# CLK_SYNTH.net
KiCad netlist of a schematic drawn in Altium Designer
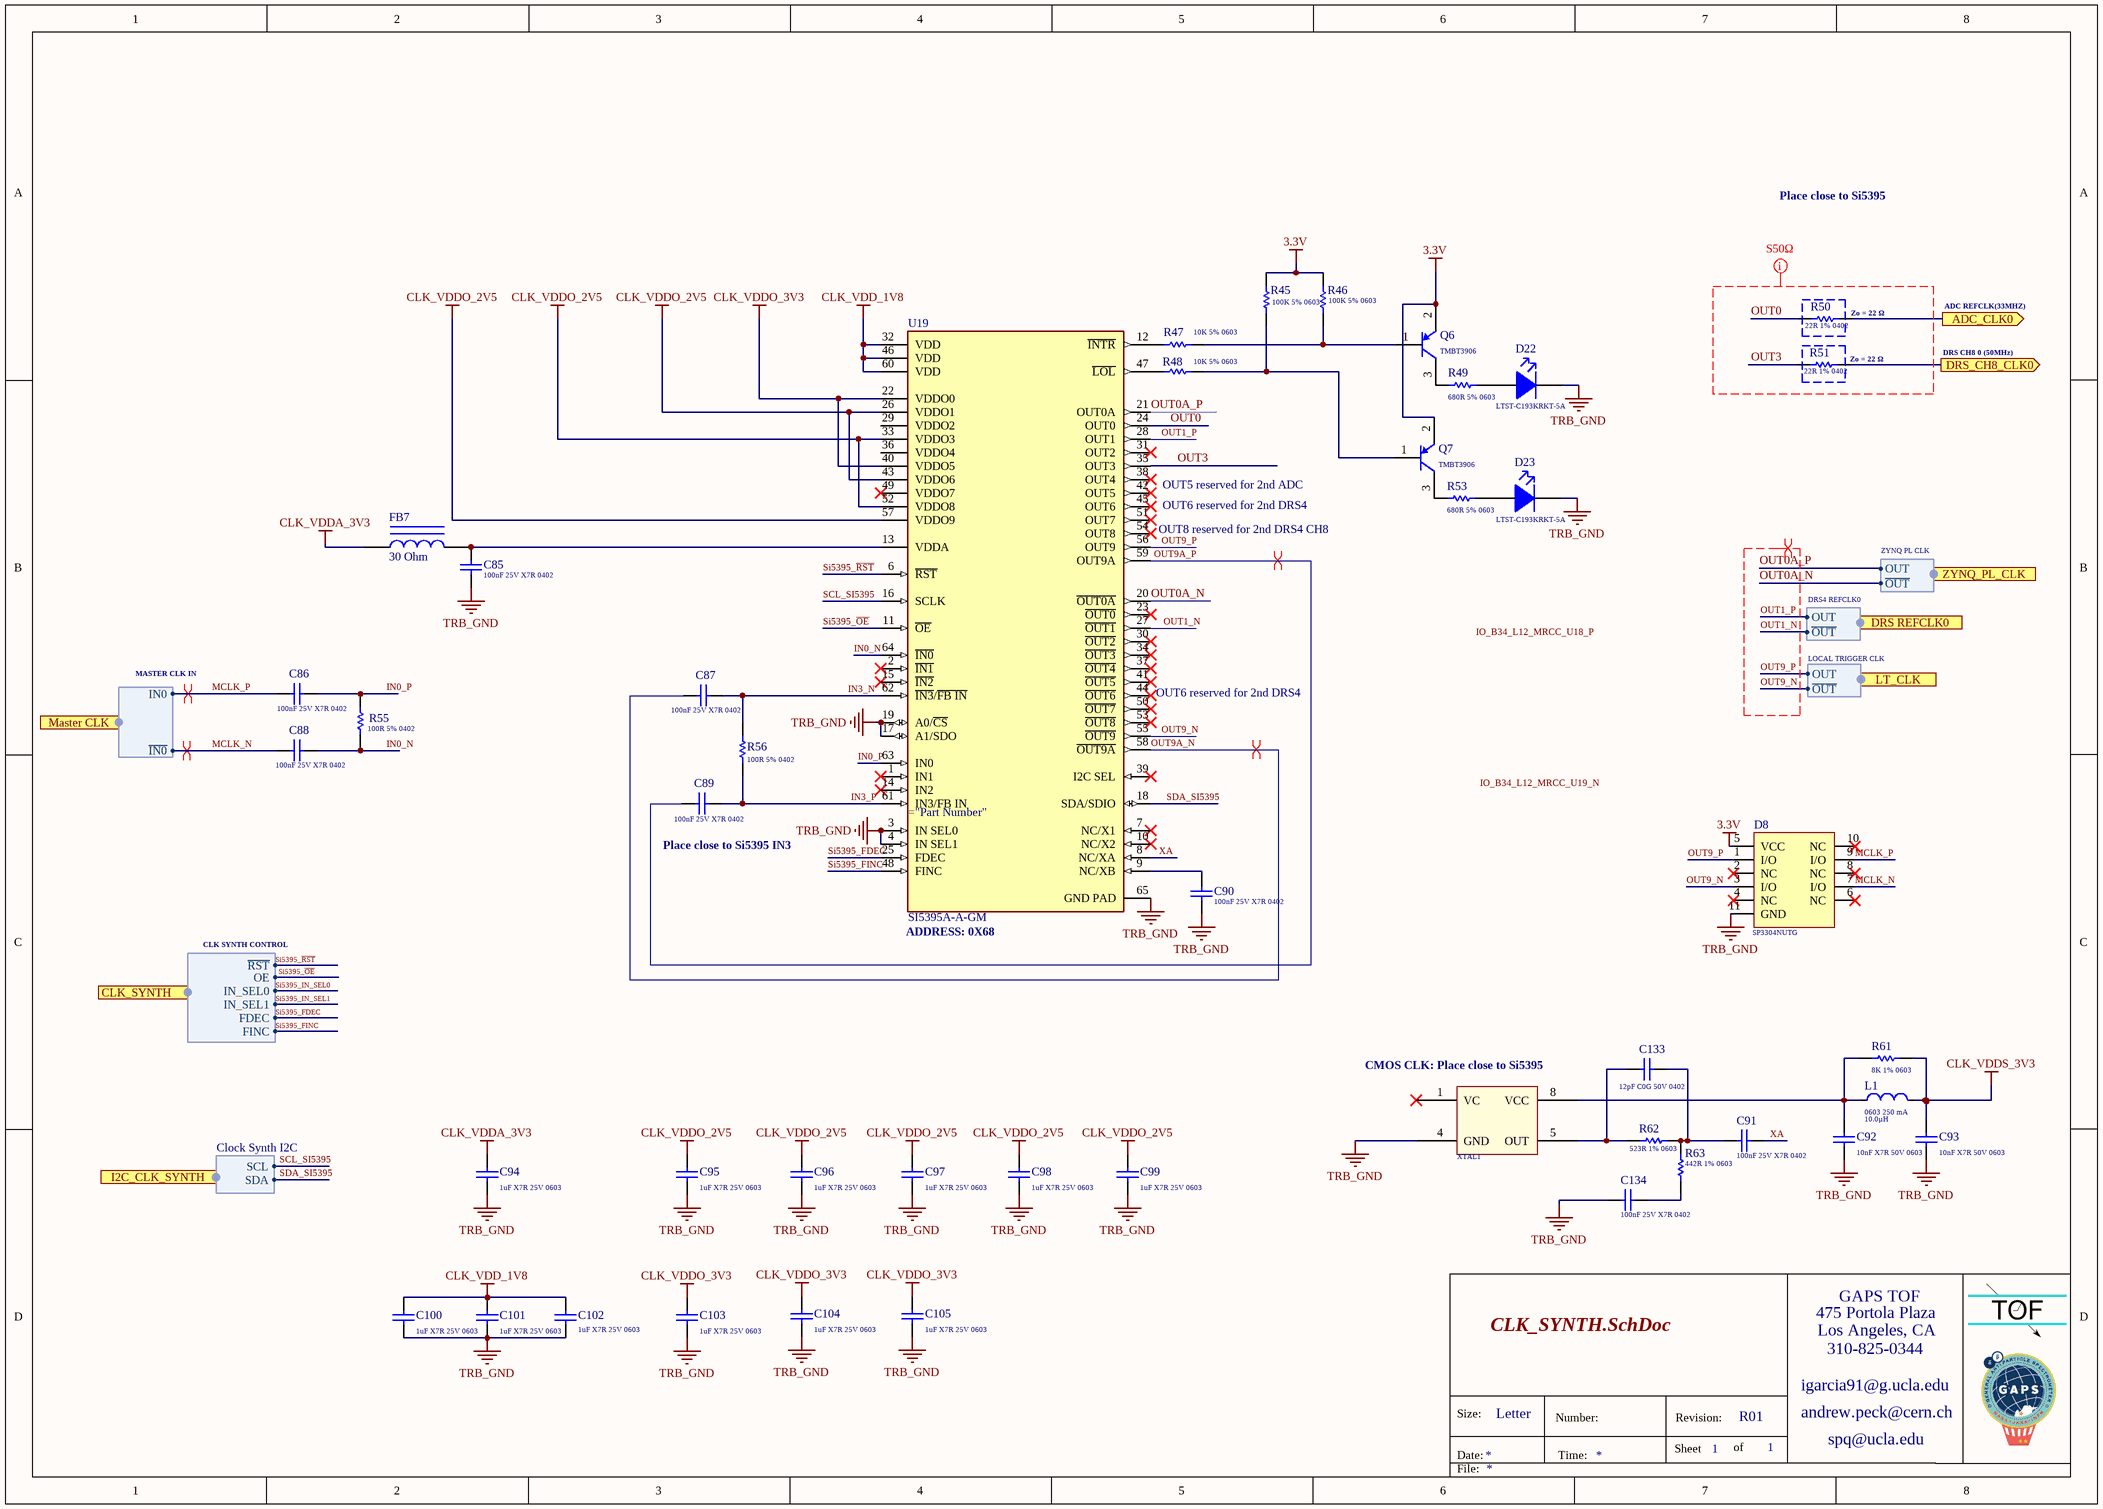
[diagram p0: CLK_SYNTH.SchDoc]

(export (version "E")
  (design (tool "Eeschema 10.0.6"))
  (components
    (comp (ref "C85")
      (value "Cap_Taiyo_Yuden_TMK105B7104KV-FR_100nF")
      (footprint "Cap_Taiyo_Yuden_TMK105B7104KV-FR_100nF")
      (description "CAP CER 100nF 25V X7R 0402")
      (fields (field (name "CAPACITANCE") "100nF 25V X7R 0402"))
      (libsource (lib "Cap_Taiyo_Yuden_TMK105B7104KV-FR_100nF") (part "Cap_Taiyo_Yuden_TMK105B7104KV-FR_100nF"))
    )
    (comp (ref "C86")
      (value "Cap_Taiyo_Yuden_TMK105B7104KV-FR_100nF")
      (footprint "Cap_Taiyo_Yuden_TMK105B7104KV-FR_100nF")
      (description "CAP CER 100nF 25V X7R 0402")
      (fields (field (name "CAPACITANCE") "100nF 25V X7R 0402"))
      (libsource (lib "Cap_Taiyo_Yuden_TMK105B7104KV-FR_100nF") (part "Cap_Taiyo_Yuden_TMK105B7104KV-FR_100nF"))
    )
    (comp (ref "C87")
      (value "Cap_Taiyo_Yuden_TMK105B7104KV-FR_100nF")
      (footprint "Cap_Taiyo_Yuden_TMK105B7104KV-FR_100nF")
      (description "CAP CER 100nF 25V X7R 0402")
      (fields (field (name "CAPACITANCE") "100nF 25V X7R 0402"))
      (libsource (lib "Cap_Taiyo_Yuden_TMK105B7104KV-FR_100nF") (part "Cap_Taiyo_Yuden_TMK105B7104KV-FR_100nF"))
    )
    (comp (ref "C88")
      (value "Cap_Taiyo_Yuden_TMK105B7104KV-FR_100nF")
      (footprint "Cap_Taiyo_Yuden_TMK105B7104KV-FR_100nF")
      (description "CAP CER 100nF 25V X7R 0402")
      (fields (field (name "CAPACITANCE") "100nF 25V X7R 0402"))
      (libsource (lib "Cap_Taiyo_Yuden_TMK105B7104KV-FR_100nF") (part "Cap_Taiyo_Yuden_TMK105B7104KV-FR_100nF"))
    )
    (comp (ref "C89")
      (value "Cap_Taiyo_Yuden_TMK105B7104KV-FR_100nF")
      (footprint "Cap_Taiyo_Yuden_TMK105B7104KV-FR_100nF")
      (description "CAP CER 100nF 25V X7R 0402")
      (fields (field (name "CAPACITANCE") "100nF 25V X7R 0402"))
      (libsource (lib "Cap_Taiyo_Yuden_TMK105B7104KV-FR_100nF") (part "Cap_Taiyo_Yuden_TMK105B7104KV-FR_100nF"))
    )
    (comp (ref "C90")
      (value "Cap_Taiyo_Yuden_TMK105B7104KV-FR_100nF")
      (footprint "Cap_Taiyo_Yuden_TMK105B7104KV-FR_100nF")
      (description "CAP CER 100nF 25V X7R 0402")
      (fields (field (name "CAPACITANCE") "100nF 25V X7R 0402"))
      (libsource (lib "Cap_Taiyo_Yuden_TMK105B7104KV-FR_100nF") (part "Cap_Taiyo_Yuden_TMK105B7104KV-FR_100nF"))
    )
    (comp (ref "C91")
      (value "Cap_Taiyo_Yuden_TMK105B7104KV-FR_100nF")
      (footprint "Cap_Taiyo_Yuden_TMK105B7104KV-FR_100nF")
      (description "CAP CER 100nF 25V X7R 0402")
      (fields (field (name "CAPACITANCE") "100nF 25V X7R 0402"))
      (libsource (lib "Cap_Taiyo_Yuden_TMK105B7104KV-FR_100nF") (part "Cap_Taiyo_Yuden_TMK105B7104KV-FR_100nF"))
    )
    (comp (ref "C92")
      (value "Cap_Kemet_C0603C103J5RACTU_eec")
      (footprint "Kemet_C0603_0")
      (description "CAP CER 10nF 50V X7R 0603")
      (fields
        (field (name "PART NUMBER") "C0603C103J5RACTU")
        (field (name "MANUFACTURER") "Kemet")
        (field (name "CAPACITANCE") "10nF X7R 50V 0603")
      )
      (libsource (lib "Cap_Kemet_C0603C103J5RACTU_10nF") (part "Cap_Kemet_C0603C103J5RACTU_eec"))
    )
    (comp (ref "C93")
      (value "Cap_Kemet_C0603C103J5RACTU_eec")
      (footprint "Kemet_C0603_0")
      (description "CAP CER 10nF 50V X7R 0603")
      (fields
        (field (name "PART NUMBER") "C0603C103J5RACTU")
        (field (name "MANUFACTURER") "Kemet")
        (field (name "CAPACITANCE") "10nF X7R 50V 0603")
      )
      (libsource (lib "Cap_Kemet_C0603C103J5RACTU_10nF") (part "Cap_Kemet_C0603C103J5RACTU_eec"))
    )
    (comp (ref "C94")
      (value "Cap_Murata_GCJ188R71E105KA01J_1uF")
      (footprint "Cap_Murata_GCJ188R71E105KA01J_1uF")
      (description "CAP CER 1uF 25V X7R 0603")
      (fields (field (name "CAPACITANCE") "1uF X7R 25V 0603"))
      (libsource (lib "Cap_Murata_GCJ188R71E105KA01J_1uF") (part "Cap_Murata_GCJ188R71E105KA01J_1uF"))
    )
    (comp (ref "C95")
      (value "Cap_Murata_GCJ188R71E105KA01J_1uF")
      (footprint "Cap_Murata_GCJ188R71E105KA01J_1uF")
      (description "CAP CER 1uF 25V X7R 0603")
      (fields (field (name "CAPACITANCE") "1uF X7R 25V 0603"))
      (libsource (lib "Cap_Murata_GCJ188R71E105KA01J_1uF") (part "Cap_Murata_GCJ188R71E105KA01J_1uF"))
    )
    (comp (ref "C96")
      (value "Cap_Murata_GCJ188R71E105KA01J_1uF")
      (footprint "Cap_Murata_GCJ188R71E105KA01J_1uF")
      (description "CAP CER 1uF 25V X7R 0603")
      (fields (field (name "CAPACITANCE") "1uF X7R 25V 0603"))
      (libsource (lib "Cap_Murata_GCJ188R71E105KA01J_1uF") (part "Cap_Murata_GCJ188R71E105KA01J_1uF"))
    )
    (comp (ref "C97")
      (value "Cap_Murata_GCJ188R71E105KA01J_1uF")
      (footprint "Cap_Murata_GCJ188R71E105KA01J_1uF")
      (description "CAP CER 1uF 25V X7R 0603")
      (fields (field (name "CAPACITANCE") "1uF X7R 25V 0603"))
      (libsource (lib "Cap_Murata_GCJ188R71E105KA01J_1uF") (part "Cap_Murata_GCJ188R71E105KA01J_1uF"))
    )
    (comp (ref "C98")
      (value "Cap_Murata_GCJ188R71E105KA01J_1uF")
      (footprint "Cap_Murata_GCJ188R71E105KA01J_1uF")
      (description "CAP CER 1uF 25V X7R 0603")
      (fields (field (name "CAPACITANCE") "1uF X7R 25V 0603"))
      (libsource (lib "Cap_Murata_GCJ188R71E105KA01J_1uF") (part "Cap_Murata_GCJ188R71E105KA01J_1uF"))
    )
    (comp (ref "C99")
      (value "Cap_Murata_GCJ188R71E105KA01J_1uF")
      (footprint "Cap_Murata_GCJ188R71E105KA01J_1uF")
      (description "CAP CER 1uF 25V X7R 0603")
      (fields (field (name "CAPACITANCE") "1uF X7R 25V 0603"))
      (libsource (lib "Cap_Murata_GCJ188R71E105KA01J_1uF") (part "Cap_Murata_GCJ188R71E105KA01J_1uF"))
    )
    (comp (ref "C100")
      (value "Cap_Murata_GCJ188R71E105KA01J_1uF")
      (footprint "Cap_Murata_GCJ188R71E105KA01J_1uF")
      (description "CAP CER 1uF 25V X7R 0603")
      (fields (field (name "CAPACITANCE") "1uF X7R 25V 0603"))
      (libsource (lib "Cap_Murata_GCJ188R71E105KA01J_1uF") (part "Cap_Murata_GCJ188R71E105KA01J_1uF"))
    )
    (comp (ref "C101")
      (value "Cap_Murata_GCJ188R71E105KA01J_1uF")
      (footprint "Cap_Murata_GCJ188R71E105KA01J_1uF")
      (description "CAP CER 1uF 25V X7R 0603")
      (fields (field (name "CAPACITANCE") "1uF X7R 25V 0603"))
      (libsource (lib "Cap_Murata_GCJ188R71E105KA01J_1uF") (part "Cap_Murata_GCJ188R71E105KA01J_1uF"))
    )
    (comp (ref "C102")
      (value "Cap_Murata_GCJ188R71E105KA01J_1uF")
      (footprint "Cap_Murata_GCJ188R71E105KA01J_1uF")
      (description "CAP CER 1uF 25V X7R 0603")
      (fields (field (name "CAPACITANCE") "1uF X7R 25V 0603"))
      (libsource (lib "Cap_Murata_GCJ188R71E105KA01J_1uF") (part "Cap_Murata_GCJ188R71E105KA01J_1uF"))
    )
    (comp (ref "C103")
      (value "Cap_Murata_GCJ188R71E105KA01J_1uF")
      (footprint "Cap_Murata_GCJ188R71E105KA01J_1uF")
      (description "CAP CER 1uF 25V X7R 0603")
      (fields (field (name "CAPACITANCE") "1uF X7R 25V 0603"))
      (libsource (lib "Cap_Murata_GCJ188R71E105KA01J_1uF") (part "Cap_Murata_GCJ188R71E105KA01J_1uF"))
    )
    (comp (ref "C104")
      (value "Cap_Murata_GCJ188R71E105KA01J_1uF")
      (footprint "Cap_Murata_GCJ188R71E105KA01J_1uF")
      (description "CAP CER 1uF 25V X7R 0603")
      (fields (field (name "CAPACITANCE") "1uF X7R 25V 0603"))
      (libsource (lib "Cap_Murata_GCJ188R71E105KA01J_1uF") (part "Cap_Murata_GCJ188R71E105KA01J_1uF"))
    )
    (comp (ref "C105")
      (value "Cap_Murata_GCJ188R71E105KA01J_1uF")
      (footprint "Cap_Murata_GCJ188R71E105KA01J_1uF")
      (description "CAP CER 1uF 25V X7R 0603")
      (fields (field (name "CAPACITANCE") "1uF X7R 25V 0603"))
      (libsource (lib "Cap_Murata_GCJ188R71E105KA01J_1uF") (part "Cap_Murata_GCJ188R71E105KA01J_1uF"))
    )
    (comp (ref "C133")
      (value "Cap_Murata_GCQ1555C1H120FB01D_12pF")
      (footprint "Cap_Murata_GCQ1555C1H120FB01D_12pF")
      (description "Multilayer Ceramic Capacitors MLCC - SMD/SMT 0402 50VDC 12pF 1% AEC-Q200")
      (fields (field (name "CAPACITANCE") "12pF C0G 50V 0402"))
      (libsource (lib "Cap_Murata_GCQ1555C1H120FB01D_12pF") (part "Cap_Murata_GCQ1555C1H120FB01D_12pF"))
    )
    (comp (ref "C134")
      (value "Cap_Taiyo_Yuden_TMK105B7104KV-FR_100nF")
      (footprint "Cap_Taiyo_Yuden_TMK105B7104KV-FR_100nF")
      (description "CAP CER 100nF 25V X7R 0402")
      (fields (field (name "CAPACITANCE") "100nF 25V X7R 0402"))
      (libsource (lib "Cap_Taiyo_Yuden_TMK105B7104KV-FR_100nF") (part "Cap_Taiyo_Yuden_TMK105B7104KV-FR_100nF"))
    )
    (comp (ref "D8")
      (value "ESD_LittleFuse_SP3304NUTG_3V3")
      (footprint "ESD_LittleFuse_SP3304NUTG_3V3")
      (description "ESD Suppressors / TVS Diodes 4CH 20A 3.3V 3.5pF Lightning Protection")
      (fields (field (name "SERIES") "SP3304NUTG"))
      (libsource (lib "ESD_LittleFuse_SP3304NUTG _3V3") (part "ESD_LittleFuse_SP3304NUTG_3V3"))
    )
    (comp (ref "D22")
      (value "LTST-C193KRKT-5A")
      (footprint "Led_Lite-On_LTST-C193KGKT-5A_Red")
      (description "Standard LEDs - SMD Red 470nm 28mcd 20mA")
      (fields (field (name "SERIES") "LTST-C193KRKT-5A"))
      (libsource (lib "Led_Lite-On_LTST-C193KGKT-5A_Red") (part "Led_Lite-On_LTST-C193KGKT-5A_Red"))
    )
    (comp (ref "D23")
      (value "LTST-C193KRKT-5A")
      (footprint "Led_Lite-On_LTST-C193KGKT-5A_Red")
      (description "Standard LEDs - SMD Red 470nm 28mcd 20mA")
      (fields (field (name "SERIES") "LTST-C193KRKT-5A"))
      (libsource (lib "Led_Lite-On_LTST-C193KGKT-5A_Red") (part "Led_Lite-On_LTST-C193KGKT-5A_Red"))
    )
    (comp (ref "FB7")
      (value "30 Ohm")
      (footprint "Feb_MURATA_BLM15AX300SZ1D_30")
      (description "Feb SMD 30 OHM 25% 3/4W 0402")
      (libsource (lib "Feb_MURATA_BLM15AX300SZ1D_30") (part "Feb_MURATA_BLM15AX300SZ1D_30"))
    )
    (comp (ref "L1")
      (value "0603 250 mA")
      (footprint "TDK_MLZ1608M100WT_0")
      (description "IND 10µH Shielded Multilayer Inductor 250mA 1.365 Ohm Max 0603 (1608 Metric)")
      (fields
        (field (name "PART NUMBER") "MLZ1608M100WT")
        (field (name "MANUFACTURER") "TDK")
        (field (name "INDUCTANCE") "10.0µH")
      )
      (libsource (lib "Ind_TDK_MLZ1608M100WT_10uH") (part "Ind_TDK_MLZ1608M100WT_eec"))
    )
    (comp (ref "Q6")
      (value "BJT_PNP_Toshiba_TMBT3906")
      (footprint "BJT_PNP_Toshiba_TMBT3906")
      (description "Bipolar Transistors - BJT Transistor for Low Freq. Amplification")
      (fields (field (name "SERIES") "TMBT3906"))
      (libsource (lib "BJT_PNP_Toshiba_TMBT3906") (part "BJT_PNP_Toshiba_TMBT3906"))
    )
    (comp (ref "Q7")
      (value "BJT_PNP_Toshiba_TMBT3906")
      (footprint "BJT_PNP_Toshiba_TMBT3906")
      (description "Bipolar Transistors - BJT Transistor for Low Freq. Amplification")
      (fields (field (name "SERIES") "TMBT3906"))
      (libsource (lib "BJT_PNP_Toshiba_TMBT3906") (part "BJT_PNP_Toshiba_TMBT3906"))
    )
    (comp (ref "R45")
      (value "100K 5% 0603")
      (footprint "RESC0603(1608)_N")
      (description "100K 0.1W 5% 0603 (1608 Metric)  SMD")
      (fields (field (name "TOLERANCE") "5 %") (field (name "POWER") "0.1 W"))
      (libsource (lib "Altium Content Vault") (part "RES"))
    )
    (comp (ref "R46")
      (value "100K 5% 0603")
      (footprint "RESC0603(1608)_N")
      (description "100K 0.1W 5% 0603 (1608 Metric)  SMD")
      (fields (field (name "TOLERANCE") "5 %") (field (name "POWER") "0.1 W"))
      (libsource (lib "Altium Content Vault") (part "RES"))
    )
    (comp (ref "R47")
      (value "10K 5% 0603")
      (footprint "RESC0603(1608)_L")
      (description "10K 0.1W 5% 0603 (1608 Metric)  SMD")
      (fields (field (name "TOLERANCE") "5 %") (field (name "POWER") "0.1 W"))
      (libsource (lib "Altium Content Vault") (part "RES"))
    )
    (comp (ref "R48")
      (value "10K 5% 0603")
      (footprint "RESC0603(1608)_L")
      (description "10K 0.1W 5% 0603 (1608 Metric)  SMD")
      (fields (field (name "TOLERANCE") "5 %") (field (name "POWER") "0.1 W"))
      (libsource (lib "Altium Content Vault") (part "RES"))
    )
    (comp (ref "R49")
      (value "680R 5% 0603")
      (footprint "RESC0603(1608)_L")
      (description "680R 0.1W 5% 0603 (1608 Metric)  SMD")
      (fields (field (name "TOLERANCE") "5 %") (field (name "POWER") "0.1 W"))
      (libsource (lib "Altium Content Vault") (part "RES"))
    )
    (comp (ref "R50")
      (value "22R 1% 0402")
      (footprint "RESC0402(1005)_L")
      (description "22R 0.063W 1% 0402 (1005 Metric)  SMD")
      (fields (field (name "TOLERANCE") "1 %") (field (name "POWER") "0.063 W"))
      (libsource (lib "Altium Content Vault") (part "RES"))
    )
    (comp (ref "R51")
      (value "22R 1% 0402")
      (footprint "RESC0402(1005)_L")
      (description "22R 0.063W 1% 0402 (1005 Metric)  SMD")
      (fields (field (name "TOLERANCE") "1 %") (field (name "POWER") "0.063 W"))
      (libsource (lib "Altium Content Vault") (part "RES"))
    )
    (comp (ref "R53")
      (value "680R 5% 0603")
      (footprint "RESC0603(1608)_L")
      (description "680R 0.1W 5% 0603 (1608 Metric)  SMD")
      (fields (field (name "TOLERANCE") "5 %") (field (name "POWER") "0.1 W"))
      (libsource (lib "Altium Content Vault") (part "RES"))
    )
    (comp (ref "R55")
      (value "100R 5% 0402")
      (footprint "RESC0402(1005)_L")
      (description "100R 0.063W 5% 0402 (1005 Metric)  SMD")
      (fields (field (name "TOLERANCE") "5 %") (field (name "POWER") "0.063 W"))
      (libsource (lib "Altium Content Vault") (part "RES"))
    )
    (comp (ref "R56")
      (value "100R 5% 0402")
      (footprint "RESC0402(1005)_L")
      (description "100R 0.063W 5% 0402 (1005 Metric)  SMD")
      (fields (field (name "TOLERANCE") "5 %") (field (name "POWER") "0.063 W"))
      (libsource (lib "Altium Content Vault") (part "RES"))
    )
    (comp (ref "R61")
      (value "8K 1% 0603")
      (footprint "Res_Yageo_RT0603BRE078KL_8K")
      (description "8K 0.1W 1% 0603 (1608 Metric)  SMD")
      (libsource (lib "Res_Yageo_RT0603BRE078KL_8K") (part "Res_Yageo_RT0603BRE078KL_8K"))
    )
    (comp (ref "R62")
      (value "Res_Vishay_CRCW0603523RFKEA_523Ohm")
      (footprint "Res_Vishay_CRCW0603523RFKEA_523Ohm")
      (description "RES SMD 523 OHM 1% 1/10W 0603")
      (fields (field (name "RESISTANCE") "523R 1% 0603"))
      (libsource (lib "Res_Vishay_CRCW0603523RFKEA_523Ohm") (part "Res_Vishay_CRCW0603523RFKEA_523Ohm"))
    )
    (comp (ref "R63")
      (value "Res_Bourns_CR0603-FX-4420ELF_442Ohm")
      (footprint "Res_Bourns_CR0603-FX-4420ELF_442Ohm")
      (description "RES SMD 442 OHM 1% 1/10W 0603")
      (fields (field (name "RESISTANCE") "442R 1% 0603"))
      (libsource (lib "Res_Bourns_CR0603-FX-4420ELF_442Ohm") (part "Res_Bourns_CR0603-FX-4420ELF_442Ohm"))
    )
    (comp (ref "U19")
      (value "IC_Silicon_Laboratories_ SI5395A-A-GM_CLK")
      (footprint "Si5395")
      (fields (field (name "SERIES") "SI5395A-A-GM"))
      (libsource (lib "SI5395A-A-GM") (part "IC_Silicon_Laboratories_ SI5395A-A-GM_CLK"))
    )
    (comp (ref "XTAL1")
      (value "TCXO_Murata_XTCLH50M000CHJA3P0_50MHz")
      (footprint "TCXO_Murata_XTCLH50M000CHJA3P0_50MHz")
      (description "TCXO Oscillators 50MHz 5x3.2x1.5mm 0.2ppm max Crystal")
      (libsource (lib "TCXO_Murata_XTCLH50M000CHJA3P0_50MHz") (part "TCXO_Murata_XTCLH50M000CHJA3P0_50MHz"))
    )
  )
  (nets
    (net (code "15") (name "/ADC_CLK0") (class "Default")
      (node (ref "R50") (pin "1") (pinfunction "1_1") (pintype "passive"))
    )
    (net (code "16") (name "/DRS_CH8_CLK0") (class "Default")
      (node (ref "R51") (pin "1") (pinfunction "1_1") (pintype "passive"))
    )
    (net (code "17") (name "/IN0_N") (class "Default")
      (node (ref "C88") (pin "2") (pinfunction "2_2") (pintype "passive"))
      (node (ref "R55") (pin "1") (pinfunction "1_1") (pintype "passive"))
      (node (ref "U19") (pin "64") (pinfunction "~{IN0}_64") (pintype "input"))
    )
    (net (code "18") (name "/IN0_P") (class "Default")
      (node (ref "C86") (pin "2") (pinfunction "2_2") (pintype "passive"))
      (node (ref "R55") (pin "2") (pinfunction "2_2") (pintype "passive"))
      (node (ref "U19") (pin "63") (pinfunction "IN0_63") (pintype "input"))
    )
    (net (code "19") (name "/IN3_N") (class "Default")
      (node (ref "C87") (pin "2") (pinfunction "2_2") (pintype "passive"))
      (node (ref "R56") (pin "2") (pinfunction "2_2") (pintype "passive"))
      (node (ref "U19") (pin "62") (pinfunction "~{IN3}/~{FB_IN}_62") (pintype "input"))
    )
    (net (code "20") (name "/IN3_P") (class "Default")
      (node (ref "C89") (pin "2") (pinfunction "2_2") (pintype "passive"))
      (node (ref "R56") (pin "1") (pinfunction "1_1") (pintype "passive"))
      (node (ref "U19") (pin "61") (pinfunction "IN3/FB_IN_61") (pintype "input"))
    )
    (net (code "23") (name "/MCLK_N") (class "Default")
      (node (ref "C88") (pin "1") (pinfunction "1_1") (pintype "passive"))
      (node (ref "D8") (pin "7") (pinfunction "I/O_7") (pintype "passive"))
    )
    (net (code "24") (name "/MCLK_P") (class "Default")
      (node (ref "C86") (pin "1") (pinfunction "1_1") (pintype "passive"))
      (node (ref "D8") (pin "9") (pinfunction "I/O_9") (pintype "passive"))
    )
    (net (code "25") (name "/OUT0") (class "Default")
      (node (ref "R50") (pin "2") (pinfunction "2_2") (pintype "passive"))
      (node (ref "U19") (pin "24") (pinfunction "OUT0_24") (pintype "output"))
    )
    (net (code "26") (name "/OUT0A_N") (class "Default")
      (node (ref "U19") (pin "20") (pinfunction "~{OUT0A}_20") (pintype "output"))
    )
    (net (code "27") (name "/OUT0A_P") (class "Default")
      (node (ref "U19") (pin "21") (pinfunction "OUT0A_21") (pintype "output"))
    )
    (net (code "28") (name "/OUT1_N") (class "Default")
      (node (ref "U19") (pin "27") (pinfunction "~{OUT1}_27") (pintype "output"))
    )
    (net (code "29") (name "/OUT1_P") (class "Default")
      (node (ref "U19") (pin "28") (pinfunction "OUT1_28") (pintype "output"))
    )
    (net (code "30") (name "/OUT3") (class "Default")
      (node (ref "R51") (pin "2") (pinfunction "2_2") (pintype "passive"))
      (node (ref "U19") (pin "35") (pinfunction "OUT3_35") (pintype "output"))
    )
    (net (code "31") (name "/OUT9A_N") (class "Default")
      (node (ref "C87") (pin "1") (pinfunction "1_1") (pintype "passive"))
      (node (ref "U19") (pin "58") (pinfunction "~{OUT9A}_58") (pintype "output"))
    )
    (net (code "32") (name "/OUT9A_P") (class "Default")
      (node (ref "C89") (pin "1") (pinfunction "1_1") (pintype "passive"))
      (node (ref "U19") (pin "59") (pinfunction "OUT9A_59") (pintype "output"))
    )
    (net (code "33") (name "/OUT9_N") (class "Default")
      (node (ref "D8") (pin "3") (pinfunction "I/O_3") (pintype "passive"))
      (node (ref "U19") (pin "55") (pinfunction "~{OUT9}_55") (pintype "output"))
    )
    (net (code "34") (name "/OUT9_P") (class "Default")
      (node (ref "D8") (pin "1") (pinfunction "I/O_1") (pintype "passive"))
      (node (ref "U19") (pin "56") (pinfunction "OUT9_56") (pintype "output"))
    )
    (net (code "35") (name "/SCL_SI5395") (class "Default")
      (node (ref "U19") (pin "16") (pinfunction "SCLK_16") (pintype "input"))
    )
    (net (code "36") (name "/SDA_SI5395") (class "Default")
      (node (ref "U19") (pin "18") (pinfunction "SDA/SDIO_18") (pintype "bidirectional"))
    )
    (net (code "37") (name "/Si5395_FDEC") (class "Default")
      (node (ref "U19") (pin "25") (pinfunction "FDEC_25") (pintype "input"))
    )
    (net (code "38") (name "/Si5395_FINC") (class "Default")
      (node (ref "U19") (pin "48") (pinfunction "FINC_48") (pintype "input"))
    )
    (net (code "41") (name "/Si5395_~{OE}") (class "Default")
      (node (ref "U19") (pin "11") (pinfunction "~{OE}_11") (pintype "input"))
    )
    (net (code "42") (name "/Si5395_~{RST}") (class "Default")
      (node (ref "U19") (pin "6") (pinfunction "~{RST}_6") (pintype "input"))
    )
    (net (code "43") (name "/XA") (class "Default")
      (node (ref "C91") (pin "2") (pinfunction "2_2") (pintype "passive"))
      (node (ref "U19") (pin "8") (pinfunction "NC/XA_8") (pintype "input"))
    )
    (net (code "50") (name "3.3V") (class "Default")
      (node (ref "D8") (pin "5") (pinfunction "VCC_5") (pintype "passive"))
      (node (ref "Q6") (pin "2") (pinfunction "E_2") (pintype "passive"))
      (node (ref "Q7") (pin "2") (pinfunction "E_2") (pintype "passive"))
      (node (ref "R45") (pin "2") (pinfunction "2_2") (pintype "passive"))
      (node (ref "R46") (pin "2") (pinfunction "2_2") (pintype "passive"))
    )
    (net (code "51") (name "CLK_VDDA_3V3") (class "Default")
      (node (ref "C94") (pin "2") (pinfunction "2_2") (pintype "passive"))
      (node (ref "FB7") (pin "1") (pinfunction "1_1") (pintype "passive"))
    )
    (net (code "52") (name "CLK_VDDO_2V5") (class "Default")
      (node (ref "C95") (pin "2") (pinfunction "2_2") (pintype "passive"))
      (node (ref "C96") (pin "2") (pinfunction "2_2") (pintype "passive"))
      (node (ref "C97") (pin "2") (pinfunction "2_2") (pintype "passive"))
      (node (ref "C98") (pin "2") (pinfunction "2_2") (pintype "passive"))
      (node (ref "C99") (pin "2") (pinfunction "2_2") (pintype "passive"))
      (node (ref "U19") (pin "26") (pinfunction "VDDO1_26") (pintype "power_in"))
      (node (ref "U19") (pin "33") (pinfunction "VDDO3_33") (pintype "power_in"))
      (node (ref "U19") (pin "43") (pinfunction "VDDO6_43") (pintype "power_in"))
      (node (ref "U19") (pin "52") (pinfunction "VDDO8_52") (pintype "power_in"))
      (node (ref "U19") (pin "57") (pinfunction "VDDO9_57") (pintype "power_in"))
    )
    (net (code "53") (name "CLK_VDDO_3V3") (class "Default")
      (node (ref "C103") (pin "2") (pinfunction "2_2") (pintype "passive"))
      (node (ref "C104") (pin "2") (pinfunction "2_2") (pintype "passive"))
      (node (ref "C105") (pin "2") (pinfunction "2_2") (pintype "passive"))
      (node (ref "U19") (pin "22") (pinfunction "VDDO0_22") (pintype "power_in"))
      (node (ref "U19") (pin "40") (pinfunction "VDDO5_40") (pintype "power_in"))
    )
    (net (code "54") (name "CLK_VDDS_3V3") (class "Default")
      (node (ref "C93") (pin "1") (pinfunction "1_1") (pintype "passive"))
      (node (ref "L1") (pin "2") (pinfunction "2_2") (pintype "passive"))
      (node (ref "R61") (pin "2") (pinfunction "2_2") (pintype "passive"))
    )
    (net (code "55") (name "CLK_VDD_1V8") (class "Default")
      (node (ref "C100") (pin "2") (pinfunction "2_2") (pintype "passive"))
      (node (ref "C101") (pin "2") (pinfunction "2_2") (pintype "passive"))
      (node (ref "C102") (pin "2") (pinfunction "2_2") (pintype "passive"))
      (node (ref "U19") (pin "32") (pinfunction "VDD_32") (pintype "power_in"))
      (node (ref "U19") (pin "46") (pinfunction "VDD_46") (pintype "power_in"))
      (node (ref "U19") (pin "60") (pinfunction "VDD_60") (pintype "power_in"))
    )
    (net (code "56") (name "Net-(C133-Pad1)") (class "Default")
      (node (ref "C133") (pin "1") (pinfunction "1_1") (pintype "passive"))
      (node (ref "C91") (pin "1") (pinfunction "1_1") (pintype "passive"))
      (node (ref "R62") (pin "2") (pinfunction "2_2") (pintype "passive"))
      (node (ref "R63") (pin "2") (pinfunction "2_2") (pintype "passive"))
    )
    (net (code "57") (name "Net-(C134-Pad2)") (class "Default")
      (node (ref "C134") (pin "2") (pinfunction "2_2") (pintype "passive"))
      (node (ref "R63") (pin "1") (pinfunction "1_1") (pintype "passive"))
    )
    (net (code "58") (name "Net-(D22-A)") (class "Default")
      (node (ref "D22") (pin "2") (pinfunction "A_2") (pintype "passive"))
      (node (ref "R49") (pin "2") (pinfunction "2_2") (pintype "passive"))
    )
    (net (code "59") (name "Net-(D23-A)") (class "Default")
      (node (ref "D23") (pin "2") (pinfunction "A_2") (pintype "passive"))
      (node (ref "R53") (pin "2") (pinfunction "2_2") (pintype "passive"))
    )
    (net (code "60") (name "Net-(Q6-B)") (class "Default")
      (node (ref "Q6") (pin "1") (pinfunction "B_1") (pintype "passive"))
      (node (ref "R46") (pin "1") (pinfunction "1_1") (pintype "passive"))
      (node (ref "R47") (pin "1") (pinfunction "1_1") (pintype "passive"))
    )
    (net (code "61") (name "Net-(Q6-C)") (class "Default")
      (node (ref "Q6") (pin "3") (pinfunction "C_3") (pintype "passive"))
      (node (ref "R49") (pin "1") (pinfunction "1_1") (pintype "passive"))
    )
    (net (code "62") (name "Net-(Q7-B)") (class "Default")
      (node (ref "Q7") (pin "1") (pinfunction "B_1") (pintype "passive"))
      (node (ref "R45") (pin "1") (pinfunction "1_1") (pintype "passive"))
      (node (ref "R48") (pin "1") (pinfunction "1_1") (pintype "passive"))
    )
    (net (code "63") (name "Net-(Q7-C)") (class "Default")
      (node (ref "Q7") (pin "3") (pinfunction "C_3") (pintype "passive"))
      (node (ref "R53") (pin "1") (pinfunction "1_1") (pintype "passive"))
    )
    (net (code "64") (name "Net-(U19-NC{slash}XB)") (class "Default")
      (node (ref "C90") (pin "2") (pinfunction "2_2") (pintype "passive"))
      (node (ref "U19") (pin "9") (pinfunction "NC/XB_9") (pintype "input"))
    )
    (net (code "65") (name "Net-(U19-VDDA)") (class "Default")
      (node (ref "C85") (pin "2") (pinfunction "2_2") (pintype "passive"))
      (node (ref "FB7") (pin "2") (pinfunction "2_2") (pintype "passive"))
      (node (ref "U19") (pin "13") (pinfunction "VDDA_13") (pintype "power_in"))
    )
    (net (code "66") (name "Net-(U19-~{INTR})") (class "Default")
      (node (ref "R47") (pin "2") (pinfunction "2_2") (pintype "passive"))
      (node (ref "U19") (pin "12") (pinfunction "~{INTR}_12") (pintype "output"))
    )
    (net (code "67") (name "Net-(U19-~{LOL})") (class "Default")
      (node (ref "R48") (pin "2") (pinfunction "2_2") (pintype "passive"))
      (node (ref "U19") (pin "47") (pinfunction "~{LOL}_47") (pintype "output"))
    )
    (net (code "68") (name "Net-(XTAL1-OUT)") (class "Default")
      (node (ref "C133") (pin "2") (pinfunction "2_2") (pintype "passive"))
      (node (ref "R62") (pin "1") (pinfunction "1_1") (pintype "passive"))
      (node (ref "XTAL1") (pin "5") (pinfunction "OUT_5") (pintype "passive"))
    )
    (net (code "69") (name "Net-(XTAL1-VCC)") (class "Default")
      (node (ref "C92") (pin "1") (pinfunction "1_1") (pintype "passive"))
      (node (ref "L1") (pin "1") (pinfunction "1_1") (pintype "passive"))
      (node (ref "R61") (pin "1") (pinfunction "1_1") (pintype "passive"))
      (node (ref "XTAL1") (pin "8") (pinfunction "VCC_8") (pintype "passive"))
    )
    (net (code "70") (name "TRB_GND") (class "Default")
      (node (ref "C100") (pin "1") (pinfunction "1_1") (pintype "passive"))
      (node (ref "C101") (pin "1") (pinfunction "1_1") (pintype "passive"))
      (node (ref "C102") (pin "1") (pinfunction "1_1") (pintype "passive"))
      (node (ref "C103") (pin "1") (pinfunction "1_1") (pintype "passive"))
      (node (ref "C104") (pin "1") (pinfunction "1_1") (pintype "passive"))
      (node (ref "C105") (pin "1") (pinfunction "1_1") (pintype "passive"))
      (node (ref "C134") (pin "1") (pinfunction "1_1") (pintype "passive"))
      (node (ref "C85") (pin "1") (pinfunction "1_1") (pintype "passive"))
      (node (ref "C90") (pin "1") (pinfunction "1_1") (pintype "passive"))
      (node (ref "C92") (pin "2") (pinfunction "2_2") (pintype "passive"))
      (node (ref "C93") (pin "2") (pinfunction "2_2") (pintype "passive"))
      (node (ref "C94") (pin "1") (pinfunction "1_1") (pintype "passive"))
      (node (ref "C95") (pin "1") (pinfunction "1_1") (pintype "passive"))
      (node (ref "C96") (pin "1") (pinfunction "1_1") (pintype "passive"))
      (node (ref "C97") (pin "1") (pinfunction "1_1") (pintype "passive"))
      (node (ref "C98") (pin "1") (pinfunction "1_1") (pintype "passive"))
      (node (ref "C99") (pin "1") (pinfunction "1_1") (pintype "passive"))
      (node (ref "D22") (pin "1") (pinfunction "K_1") (pintype "passive"))
      (node (ref "D23") (pin "1") (pinfunction "K_1") (pintype "passive"))
      (node (ref "D8") (pin "11") (pinfunction "GND_11") (pintype "passive"))
      (node (ref "U19") (pin "17") (pinfunction "A1/SDO_17") (pintype "bidirectional"))
      (node (ref "U19") (pin "19") (pinfunction "A0/~{CS}_19") (pintype "bidirectional"))
      (node (ref "U19") (pin "3") (pinfunction "IN_SEL0_3") (pintype "input"))
      (node (ref "U19") (pin "4") (pinfunction "IN_SEL1_4") (pintype "input"))
      (node (ref "U19") (pin "65") (pinfunction "GND_PAD_65") (pintype "power_in"))
      (node (ref "XTAL1") (pin "4") (pinfunction "GND_4") (pintype "passive"))
    )
    (net (code "71") (name "unconnected-(D8-NC-Pad2)") (class "Default")
      (node (ref "D8") (pin "2") (pinfunction "NC_2") (pintype "passive+no_connect"))
    )
    (net (code "72") (name "unconnected-(D8-NC-Pad4)") (class "Default")
      (node (ref "D8") (pin "4") (pinfunction "NC_4") (pintype "passive+no_connect"))
    )
    (net (code "73") (name "unconnected-(D8-NC-Pad6)") (class "Default")
      (node (ref "D8") (pin "6") (pinfunction "NC_6") (pintype "passive+no_connect"))
    )
    (net (code "74") (name "unconnected-(D8-NC-Pad8)") (class "Default")
      (node (ref "D8") (pin "8") (pinfunction "NC_8") (pintype "passive+no_connect"))
    )
    (net (code "75") (name "unconnected-(D8-NC-Pad10)") (class "Default")
      (node (ref "D8") (pin "10") (pinfunction "NC_10") (pintype "passive+no_connect"))
    )
    (net (code "76") (name "unconnected-(U19-I2C_SEL-Pad39)") (class "Default")
      (node (ref "U19") (pin "39") (pinfunction "I2C_SEL_39") (pintype "input+no_connect"))
    )
    (net (code "77") (name "unconnected-(U19-IN1-Pad1)") (class "Default")
      (node (ref "U19") (pin "1") (pinfunction "IN1_1") (pintype "input+no_connect"))
    )
    (net (code "78") (name "unconnected-(U19-IN2-Pad14)") (class "Default")
      (node (ref "U19") (pin "14") (pinfunction "IN2_14") (pintype "input+no_connect"))
    )
    (net (code "79") (name "unconnected-(U19-NC{slash}X1-Pad7)") (class "Default")
      (node (ref "U19") (pin "7") (pinfunction "NC/X1_7") (pintype "input+no_connect"))
    )
    (net (code "80") (name "unconnected-(U19-NC{slash}X2-Pad10)") (class "Default")
      (node (ref "U19") (pin "10") (pinfunction "NC/X2_10") (pintype "input+no_connect"))
    )
    (net (code "81") (name "unconnected-(U19-OUT2-Pad31)") (class "Default")
      (node (ref "U19") (pin "31") (pinfunction "OUT2_31") (pintype "output+no_connect"))
    )
    (net (code "82") (name "unconnected-(U19-OUT4-Pad38)") (class "Default")
      (node (ref "U19") (pin "38") (pinfunction "OUT4_38") (pintype "output+no_connect"))
    )
    (net (code "83") (name "unconnected-(U19-OUT5-Pad42)") (class "Default")
      (node (ref "U19") (pin "42") (pinfunction "OUT5_42") (pintype "output+no_connect"))
    )
    (net (code "84") (name "unconnected-(U19-OUT6-Pad45)") (class "Default")
      (node (ref "U19") (pin "45") (pinfunction "OUT6_45") (pintype "output+no_connect"))
    )
    (net (code "85") (name "unconnected-(U19-OUT7-Pad51)") (class "Default")
      (node (ref "U19") (pin "51") (pinfunction "OUT7_51") (pintype "output+no_connect"))
    )
    (net (code "86") (name "unconnected-(U19-OUT8-Pad54)") (class "Default")
      (node (ref "U19") (pin "54") (pinfunction "OUT8_54") (pintype "output+no_connect"))
    )
    (net (code "87") (name "unconnected-(U19-VDDO2-Pad29)") (class "Default")
      (node (ref "U19") (pin "29") (pinfunction "VDDO2_29") (pintype "power_in"))
    )
    (net (code "88") (name "unconnected-(U19-VDDO4-Pad36)") (class "Default")
      (node (ref "U19") (pin "36") (pinfunction "VDDO4_36") (pintype "power_in"))
    )
    (net (code "89") (name "unconnected-(U19-VDDO7-Pad49)") (class "Default")
      (node (ref "U19") (pin "49") (pinfunction "VDDO7_49") (pintype "power_in+no_connect"))
    )
    (net (code "90") (name "unconnected-(U19-~{IN1}-Pad2)") (class "Default")
      (node (ref "U19") (pin "2") (pinfunction "~{IN1}_2") (pintype "input+no_connect"))
    )
    (net (code "91") (name "unconnected-(U19-~{IN2}-Pad15)") (class "Default")
      (node (ref "U19") (pin "15") (pinfunction "~{IN2}_15") (pintype "input+no_connect"))
    )
    (net (code "92") (name "unconnected-(U19-~{OUT0}-Pad23)") (class "Default")
      (node (ref "U19") (pin "23") (pinfunction "~{OUT0}_23") (pintype "output+no_connect"))
    )
    (net (code "93") (name "unconnected-(U19-~{OUT2}-Pad30)") (class "Default")
      (node (ref "U19") (pin "30") (pinfunction "~{OUT2}_30") (pintype "output+no_connect"))
    )
    (net (code "94") (name "unconnected-(U19-~{OUT3}-Pad34)") (class "Default")
      (node (ref "U19") (pin "34") (pinfunction "~{OUT3}_34") (pintype "output+no_connect"))
    )
    (net (code "95") (name "unconnected-(U19-~{OUT4}-Pad37)") (class "Default")
      (node (ref "U19") (pin "37") (pinfunction "~{OUT4}_37") (pintype "output+no_connect"))
    )
    (net (code "96") (name "unconnected-(U19-~{OUT5}-Pad41)") (class "Default")
      (node (ref "U19") (pin "41") (pinfunction "~{OUT5}_41") (pintype "output+no_connect"))
    )
    (net (code "97") (name "unconnected-(U19-~{OUT6}-Pad44)") (class "Default")
      (node (ref "U19") (pin "44") (pinfunction "~{OUT6}_44") (pintype "output+no_connect"))
    )
    (net (code "98") (name "unconnected-(U19-~{OUT7}-Pad50)") (class "Default")
      (node (ref "U19") (pin "50") (pinfunction "~{OUT7}_50") (pintype "output+no_connect"))
    )
    (net (code "99") (name "unconnected-(U19-~{OUT8}-Pad53)") (class "Default")
      (node (ref "U19") (pin "53") (pinfunction "~{OUT8}_53") (pintype "output+no_connect"))
    )
    (net (code "100") (name "unconnected-(XTAL1-VC-Pad1)") (class "Default")
      (node (ref "XTAL1") (pin "1") (pinfunction "VC_1") (pintype "passive+no_connect"))
    )
  )
)
